# 008_ConsumptionBoard.net
KiCad netlist of a schematic drawn in Altium Designer
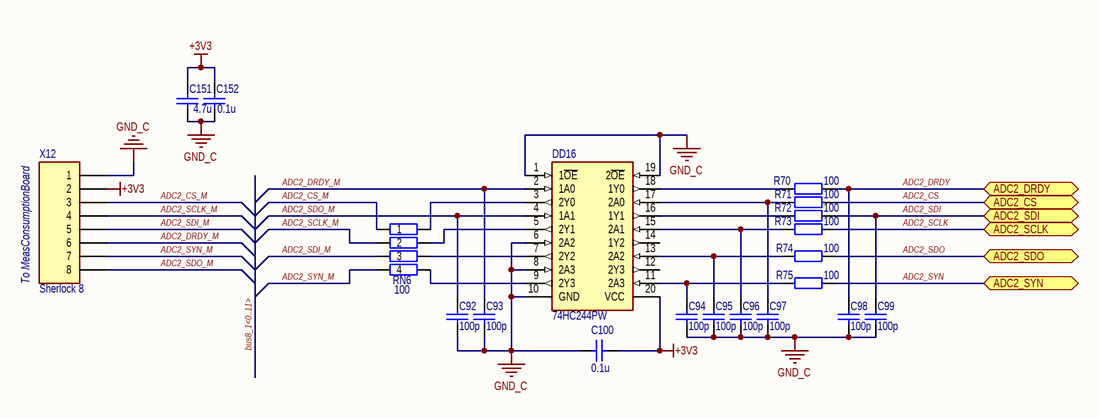
[diagram p0: 008_ConsumptionBoard.SchDoc]

(export (version "E")
  (design (tool "Eeschema 10.0.6"))
  (components
    (comp (ref "C92")
      (value "100p")
      (footprint "mainLib:SMD_C_0603")
      (description "SMD C 0603 MURATA 100V 5% NP0")
      (fields (field (name "PARTNUMBER") "GRM1885C2A101JA01") (field (name "MANUFACTURER") "MURATA"))
      (libsource (lib "mainRCLib") (part "C0603 100p 100V 5%"))
    )
    (comp (ref "C93")
      (value "100p")
      (footprint "mainLib:SMD_C_0603")
      (description "SMD C 0603 MURATA 100V 5% NP0")
      (fields (field (name "PARTNUMBER") "GRM1885C2A101JA01") (field (name "MANUFACTURER") "MURATA"))
      (libsource (lib "mainRCLib") (part "C0603 100p 100V 5%"))
    )
    (comp (ref "C94")
      (value "100p")
      (footprint "mainLib:SMD_C_0603")
      (description "SMD C 0603 MURATA 100V 5% NP0")
      (fields (field (name "PARTNUMBER") "GRM1885C2A101JA01") (field (name "MANUFACTURER") "MURATA"))
      (libsource (lib "mainRCLib") (part "C0603 100p 100V 5%"))
    )
    (comp (ref "C95")
      (value "100p")
      (footprint "mainLib:SMD_C_0603")
      (description "SMD C 0603 MURATA 100V 5% NP0")
      (fields (field (name "PARTNUMBER") "GRM1885C2A101JA01") (field (name "MANUFACTURER") "MURATA"))
      (libsource (lib "mainRCLib") (part "C0603 100p 100V 5%"))
    )
    (comp (ref "C96")
      (value "100p")
      (footprint "mainLib:SMD_C_0603")
      (description "SMD C 0603 MURATA 100V 5% NP0")
      (fields (field (name "PARTNUMBER") "GRM1885C2A101JA01") (field (name "MANUFACTURER") "MURATA"))
      (libsource (lib "mainRCLib") (part "C0603 100p 100V 5%"))
    )
    (comp (ref "C97")
      (value "100p")
      (footprint "mainLib:SMD_C_0603")
      (description "SMD C 0603 MURATA 100V 5% NP0")
      (fields (field (name "PARTNUMBER") "GRM1885C2A101JA01") (field (name "MANUFACTURER") "MURATA"))
      (libsource (lib "mainRCLib") (part "C0603 100p 100V 5%"))
    )
    (comp (ref "C98")
      (value "100p")
      (footprint "mainLib:SMD_C_0603")
      (description "SMD C 0603 MURATA 100V 5% NP0")
      (fields (field (name "PARTNUMBER") "GRM1885C2A101JA01") (field (name "MANUFACTURER") "MURATA"))
      (libsource (lib "mainRCLib") (part "C0603 100p 100V 5%"))
    )
    (comp (ref "C99")
      (value "100p")
      (footprint "mainLib:SMD_C_0603")
      (description "SMD C 0603 MURATA 100V 5% NP0")
      (fields (field (name "PARTNUMBER") "GRM1885C2A101JA01") (field (name "MANUFACTURER") "MURATA"))
      (libsource (lib "mainRCLib") (part "C0603 100p 100V 5%"))
    )
    (comp (ref "C100")
      (value "0.1u")
      (footprint "mainLib:SMD_C_0603")
      (description "SMD C 0603 MURATA 50V 10% X7R")
      (fields (field (name "PARTNUMBER") "GRM188R71H104K") (field (name "MANUFACTURER") "MURATA"))
      (libsource (lib "mainRCLib") (part "C0603 0.1u 50V 10%"))
    )
    (comp (ref "C151")
      (value "4.7u")
      (footprint "mainLib:SMD_C_0805")
      (description "SMD C 0805 MURATA 50V 5% NP0")
      (fields (field (name "PARTNUMBER") "GRM21BR61E475M") (field (name "MANUFACTURER") "MURATA"))
      (libsource (lib "mainRCLib") (part "C0805 4.7u 25V 20%  X5R"))
    )
    (comp (ref "C152")
      (value "0.1u")
      (footprint "mainLib:SMD_C_0603")
      (description "SMD C 0603 MURATA 50V 10% X7R")
      (fields (field (name "PARTNUMBER") "GRM188R71H104K") (field (name "MANUFACTURER") "MURATA"))
      (libsource (lib "mainRCLib") (part "C0603 0.1u 50V 10%"))
    )
    (comp (ref "DD16")
      (value "74HC244PW")
      (footprint "mainLib:TSSOP20")
      (description "Octal Buffer/Line Driver with 3-State Outputs, PW0020A")
      (fields (field (name "MANUFACTURER") "NXP"))
      (libsource (lib "mainLib") (part "74HC244PW"))
    )
    (comp (ref "R70")
      (value "100")
      (footprint "SMD_R_0603")
      (description "SMD R 0603 VISHAY 0.1W 75V 1% 100ppm")
      (fields (field (name "PARTNUMBER") "CRCW0603100RFK") (field (name "MANUFACTURER") "VISHAY"))
      (libsource (lib "mainRCLib") (part "R0603 100 1%"))
    )
    (comp (ref "R71")
      (value "100")
      (footprint "SMD_R_0603")
      (description "SMD R 0603 VISHAY 0.1W 75V 1% 100ppm")
      (fields (field (name "PARTNUMBER") "CRCW0603100RFK") (field (name "MANUFACTURER") "VISHAY"))
      (libsource (lib "mainRCLib") (part "R0603 100 1%"))
    )
    (comp (ref "R72")
      (value "100")
      (footprint "SMD_R_0603")
      (description "SMD R 0603 VISHAY 0.1W 75V 1% 100ppm")
      (fields (field (name "PARTNUMBER") "CRCW0603100RFK") (field (name "MANUFACTURER") "VISHAY"))
      (libsource (lib "mainRCLib") (part "R0603 100 1%"))
    )
    (comp (ref "R73")
      (value "100")
      (footprint "SMD_R_0603")
      (description "SMD R 0603 VISHAY 0.1W 75V 1% 100ppm")
      (fields (field (name "PARTNUMBER") "CRCW0603100RFK") (field (name "MANUFACTURER") "VISHAY"))
      (libsource (lib "mainRCLib") (part "R0603 100 1%"))
    )
    (comp (ref "R74")
      (value "100")
      (footprint "SMD_R_0603")
      (description "SMD R 0603 VISHAY 0.1W 75V 1% 100ppm")
      (fields (field (name "PARTNUMBER") "CRCW0603100RFK") (field (name "MANUFACTURER") "VISHAY"))
      (libsource (lib "mainRCLib") (part "R0603 100 1%"))
    )
    (comp (ref "R75")
      (value "100")
      (footprint "SMD_R_0603")
      (description "SMD R 0603 VISHAY 0.1W 75V 1% 100ppm")
      (fields (field (name "PARTNUMBER") "CRCW0603100RFK") (field (name "MANUFACTURER") "VISHAY"))
      (libsource (lib "mainRCLib") (part "R0603 100 1%"))
    )
    (comp (ref "RN6")
      (value "100")
      (footprint "mainLib:CRA06S")
      (description "SMD RESISTOR ARRAY VISHAY 0.063W 50V 1% 100ppm")
      (fields (field (name "PARTNUMBER") "CRA06S083100RF") (field (name "MANUFACTURER") "VISHAY"))
      (libsource (lib "mainRCLib") (part "CRA06S 4x100 1%"))
    )
    (comp (ref "X12")
      (value "Sherlock 8")
      (footprint "mainLib:35362-0850")
      (description "Sherlock 8 Side, 2A 125V 2mm")
      (fields (field (name "PARTNUMBER") "35362-0850") (field (name "MANUFACTURER") "MOLEX"))
      (libsource (lib "mainLib") (part "35362-0850"))
    )
  )
  (nets
    (net (code "2") (name "+3V3") (class "Default")
      (node (ref "C100") (pin "2") (pinfunction "2_2") (pintype "passive"))
      (node (ref "C151") (pin "2") (pinfunction "2_2") (pintype "passive"))
      (node (ref "C152") (pin "2") (pinfunction "2_2") (pintype "passive"))
      (node (ref "DD16") (pin "20") (pinfunction "VCC_20") (pintype "power_in"))
      (node (ref "X12") (pin "2") (pinfunction "2_2") (pintype "passive"))
    )
    (net (code "3") (name "/ADC2_CS") (class "Default")
      (node (ref "R71") (pin "2") (pinfunction "2_2") (pintype "passive"))
    )
    (net (code "4") (name "/ADC2_CS_M") (class "Default")
      (node (ref "RN6") (pin "1") (pinfunction "1_1") (pintype "passive"))
      (node (ref "X12") (pin "3") (pinfunction "3_3") (pintype "passive"))
    )
    (net (code "5") (name "/ADC2_DRDY") (class "Default")
      (node (ref "C98") (pin "1") (pinfunction "1_1") (pintype "passive"))
      (node (ref "R70") (pin "2") (pinfunction "2_2") (pintype "passive"))
    )
    (net (code "6") (name "/ADC2_DRDY_M") (class "Default")
      (node (ref "C93") (pin "1") (pinfunction "1_1") (pintype "passive"))
      (node (ref "DD16") (pin "2") (pinfunction "1A0_2") (pintype "input"))
      (node (ref "X12") (pin "6") (pinfunction "6_6") (pintype "passive"))
    )
    (net (code "7") (name "/ADC2_SCLK") (class "Default")
      (node (ref "R73") (pin "2") (pinfunction "2_2") (pintype "passive"))
    )
    (net (code "8") (name "/ADC2_SCLK_M") (class "Default")
      (node (ref "RN6") (pin "2") (pinfunction "2_2") (pintype "passive"))
      (node (ref "X12") (pin "4") (pinfunction "4_4") (pintype "passive"))
    )
    (net (code "9") (name "/ADC2_SDI") (class "Default")
      (node (ref "C99") (pin "1") (pinfunction "1_1") (pintype "passive"))
      (node (ref "R72") (pin "2") (pinfunction "2_2") (pintype "passive"))
    )
    (net (code "10") (name "/ADC2_SDI_M") (class "Default")
      (node (ref "RN6") (pin "3") (pinfunction "3_3") (pintype "passive"))
      (node (ref "X12") (pin "5") (pinfunction "5_5") (pintype "passive"))
    )
    (net (code "11") (name "/ADC2_SDO") (class "Default")
      (node (ref "R74") (pin "2") (pinfunction "2_2") (pintype "passive"))
    )
    (net (code "12") (name "/ADC2_SDO_M") (class "Default")
      (node (ref "C92") (pin "1") (pinfunction "1_1") (pintype "passive"))
      (node (ref "DD16") (pin "4") (pinfunction "1A1_4") (pintype "input"))
      (node (ref "X12") (pin "8") (pinfunction "8_8") (pintype "passive"))
    )
    (net (code "13") (name "/ADC2_SYN") (class "Default")
      (node (ref "R75") (pin "2") (pinfunction "2_2") (pintype "passive"))
    )
    (net (code "14") (name "/ADC2_SYN_M") (class "Default")
      (node (ref "RN6") (pin "4") (pinfunction "4_4") (pintype "passive"))
      (node (ref "X12") (pin "7") (pinfunction "7_7") (pintype "passive"))
    )
    (net (code "16") (name "GND_C") (class "Default")
      (node (ref "C100") (pin "1") (pinfunction "1_1") (pintype "passive"))
      (node (ref "C151") (pin "1") (pinfunction "1_1") (pintype "passive"))
      (node (ref "C152") (pin "1") (pinfunction "1_1") (pintype "passive"))
      (node (ref "C92") (pin "2") (pinfunction "2_2") (pintype "passive"))
      (node (ref "C93") (pin "2") (pinfunction "2_2") (pintype "passive"))
      (node (ref "C94") (pin "2") (pinfunction "2_2") (pintype "passive"))
      (node (ref "C95") (pin "2") (pinfunction "2_2") (pintype "passive"))
      (node (ref "C96") (pin "2") (pinfunction "2_2") (pintype "passive"))
      (node (ref "C97") (pin "2") (pinfunction "2_2") (pintype "passive"))
      (node (ref "C98") (pin "2") (pinfunction "2_2") (pintype "passive"))
      (node (ref "C99") (pin "2") (pinfunction "2_2") (pintype "passive"))
      (node (ref "DD16") (pin "1") (pinfunction "1~{OE}_1") (pintype "input"))
      (node (ref "DD16") (pin "10") (pinfunction "GND_10") (pintype "power_in"))
      (node (ref "DD16") (pin "19") (pinfunction "2~{OE}_19") (pintype "input"))
      (node (ref "DD16") (pin "6") (pinfunction "2A2_6") (pintype "input"))
      (node (ref "DD16") (pin "8") (pinfunction "2A3_8") (pintype "input"))
      (node (ref "X12") (pin "1") (pinfunction "1_1") (pintype "passive"))
    )
    (net (code "17") (name "Net-(C94-Pad1)") (class "Default")
      (node (ref "C94") (pin "1") (pinfunction "1_1") (pintype "passive"))
      (node (ref "DD16") (pin "11") (pinfunction "2A3_11") (pintype "input"))
      (node (ref "R75") (pin "1") (pinfunction "1_1") (pintype "passive"))
    )
    (net (code "18") (name "Net-(C95-Pad1)") (class "Default")
      (node (ref "C95") (pin "1") (pinfunction "1_1") (pintype "passive"))
      (node (ref "DD16") (pin "13") (pinfunction "2A2_13") (pintype "input"))
      (node (ref "R74") (pin "1") (pinfunction "1_1") (pintype "passive"))
    )
    (net (code "19") (name "Net-(DD16-1Y0)") (class "Default")
      (node (ref "DD16") (pin "18") (pinfunction "1Y0_18") (pintype "output"))
      (node (ref "R70") (pin "1") (pinfunction "1_1") (pintype "passive"))
    )
    (net (code "20") (name "Net-(DD16-1Y1)") (class "Default")
      (node (ref "DD16") (pin "16") (pinfunction "1Y1_16") (pintype "output"))
      (node (ref "R72") (pin "1") (pinfunction "1_1") (pintype "passive"))
    )
    (net (code "21") (name "Net-(DD16-2A0)") (class "Default")
      (node (ref "C97") (pin "1") (pinfunction "1_1") (pintype "passive"))
      (node (ref "DD16") (pin "17") (pinfunction "2A0_17") (pintype "input"))
      (node (ref "R71") (pin "1") (pinfunction "1_1") (pintype "passive"))
    )
    (net (code "22") (name "Net-(DD16-2A1)") (class "Default")
      (node (ref "C96") (pin "1") (pinfunction "1_1") (pintype "passive"))
      (node (ref "DD16") (pin "15") (pinfunction "2A1_15") (pintype "input"))
      (node (ref "R73") (pin "1") (pinfunction "1_1") (pintype "passive"))
    )
    (net (code "23") (name "Net-(DD16-2Y0)") (class "Default")
      (node (ref "DD16") (pin "3") (pinfunction "2Y0_3") (pintype "output"))
      (node (ref "RN6") (pin "8") (pinfunction "8_8") (pintype "passive"))
    )
    (net (code "24") (name "Net-(DD16-2Y1)") (class "Default")
      (node (ref "DD16") (pin "5") (pinfunction "2Y1_5") (pintype "output"))
      (node (ref "RN6") (pin "7") (pinfunction "7_7") (pintype "passive"))
    )
    (net (code "25") (name "Net-(DD16-2Y2)") (class "Default")
      (node (ref "DD16") (pin "7") (pinfunction "2Y2_7") (pintype "output"))
      (node (ref "RN6") (pin "6") (pinfunction "6_6") (pintype "passive"))
    )
    (net (code "26") (name "Net-(DD16-2Y3-Pad9)") (class "Default")
      (node (ref "DD16") (pin "9") (pinfunction "2Y3_9") (pintype "output"))
      (node (ref "RN6") (pin "5") (pinfunction "5_5") (pintype "passive"))
    )
    (net (code "27") (name "unconnected-(DD16-1Y2-Pad14)") (class "Default")
      (node (ref "DD16") (pin "14") (pinfunction "1Y2_14") (pintype "output"))
    )
    (net (code "28") (name "unconnected-(DD16-2Y3-Pad12)") (class "Default")
      (node (ref "DD16") (pin "12") (pinfunction "2Y3_12") (pintype "output"))
    )
  )
)
